# FW2-17-LEDLevelDisplay.net
KiCad netlist of a schematic drawn in EAGLE
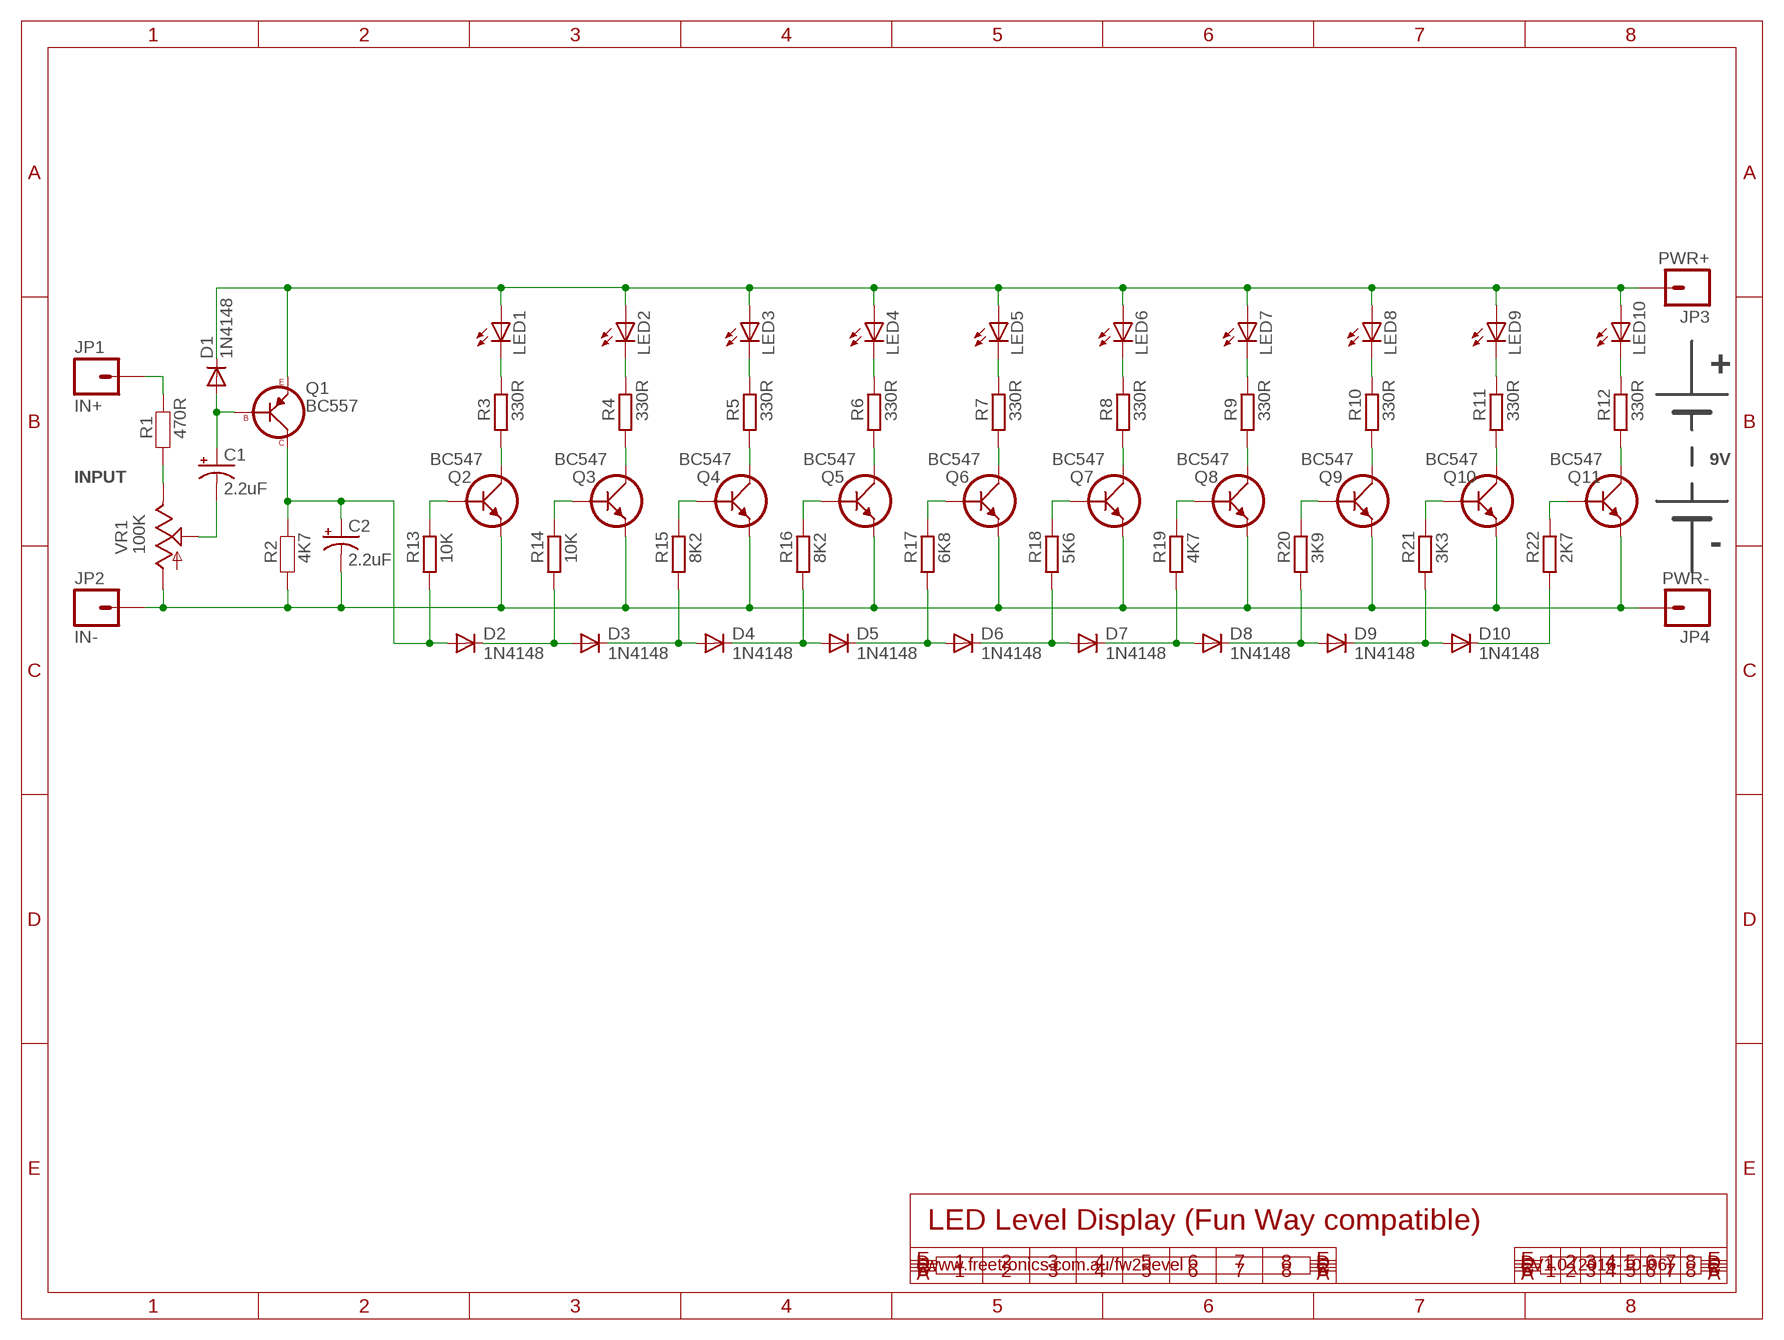
[diagram p0: schematic, sheet 1]

(export (version "E")
  (design (tool "Eeschema 10.0.6"))
  (components
    (comp (ref "C1")
      (value "2.2uF")
      (footprint "eagle-import:CPOL-RADIAL-100UF-25V")
      (libsource (lib "eagle-import") (part "CAP_POLPTH1"))
    )
    (comp (ref "C2")
      (value "2.2uF")
      (footprint "eagle-import:CPOL-RADIAL-100UF-25V")
      (libsource (lib "eagle-import") (part "CAP_POLPTH1"))
    )
    (comp (ref "D1")
      (value "1N4148")
      (footprint "eagle-import:DIODE-1N914")
      (libsource (lib "eagle-import") (part "DIODE1N914"))
    )
    (comp (ref "D2")
      (value "1N4148")
      (footprint "eagle-import:DIODE-1N914")
      (libsource (lib "eagle-import") (part "DIODE1N914"))
    )
    (comp (ref "D3")
      (value "1N4148")
      (footprint "eagle-import:DIODE-1N914")
      (libsource (lib "eagle-import") (part "DIODE1N914"))
    )
    (comp (ref "D4")
      (value "1N4148")
      (footprint "eagle-import:DIODE-1N914")
      (libsource (lib "eagle-import") (part "DIODE1N914"))
    )
    (comp (ref "D5")
      (value "1N4148")
      (footprint "eagle-import:DIODE-1N914")
      (libsource (lib "eagle-import") (part "DIODE1N914"))
    )
    (comp (ref "D6")
      (value "1N4148")
      (footprint "eagle-import:DIODE-1N914")
      (libsource (lib "eagle-import") (part "DIODE1N914"))
    )
    (comp (ref "D7")
      (value "1N4148")
      (footprint "eagle-import:DIODE-1N914")
      (libsource (lib "eagle-import") (part "DIODE1N914"))
    )
    (comp (ref "D8")
      (value "1N4148")
      (footprint "eagle-import:DIODE-1N914")
      (libsource (lib "eagle-import") (part "DIODE1N914"))
    )
    (comp (ref "D9")
      (value "1N4148")
      (footprint "eagle-import:DIODE-1N914")
      (libsource (lib "eagle-import") (part "DIODE1N914"))
    )
    (comp (ref "D10")
      (value "1N4148")
      (footprint "eagle-import:DIODE-1N914")
      (libsource (lib "eagle-import") (part "DIODE1N914"))
    )
    (comp (ref "JP1")
      (value "IN+")
      (footprint "eagle-import:1X01")
      (libsource (lib "eagle-import") (part "M01PTH"))
    )
    (comp (ref "JP2")
      (value "IN-")
      (footprint "eagle-import:1X01")
      (libsource (lib "eagle-import") (part "M01PTH"))
    )
    (comp (ref "JP3")
      (value "PWR+")
      (footprint "eagle-import:1X01")
      (libsource (lib "eagle-import") (part "M01PTH"))
    )
    (comp (ref "JP4")
      (value "PWR-")
      (footprint "eagle-import:1X01")
      (libsource (lib "eagle-import") (part "M01PTH"))
    )
    (comp (ref "LED1")
      (value "LED5MM")
      (footprint "eagle-import:LED5MM")
      (libsource (lib "eagle-import") (part "LED5MM"))
    )
    (comp (ref "LED2")
      (value "LED5MM")
      (footprint "eagle-import:LED5MM")
      (libsource (lib "eagle-import") (part "LED5MM"))
    )
    (comp (ref "LED3")
      (value "LED5MM")
      (footprint "eagle-import:LED5MM")
      (libsource (lib "eagle-import") (part "LED5MM"))
    )
    (comp (ref "LED4")
      (value "LED5MM")
      (footprint "eagle-import:LED5MM")
      (libsource (lib "eagle-import") (part "LED5MM"))
    )
    (comp (ref "LED5")
      (value "LED5MM")
      (footprint "eagle-import:LED5MM")
      (libsource (lib "eagle-import") (part "LED5MM"))
    )
    (comp (ref "LED6")
      (value "LED5MM")
      (footprint "eagle-import:LED5MM")
      (libsource (lib "eagle-import") (part "LED5MM"))
    )
    (comp (ref "LED7")
      (value "LED5MM")
      (footprint "eagle-import:LED5MM")
      (libsource (lib "eagle-import") (part "LED5MM"))
    )
    (comp (ref "LED8")
      (value "LED5MM")
      (footprint "eagle-import:LED5MM")
      (libsource (lib "eagle-import") (part "LED5MM"))
    )
    (comp (ref "LED9")
      (value "LED5MM")
      (footprint "eagle-import:LED5MM")
      (libsource (lib "eagle-import") (part "LED5MM"))
    )
    (comp (ref "LED10")
      (value "LED5MM")
      (footprint "eagle-import:LED5MM")
      (libsource (lib "eagle-import") (part "LED5MM"))
    )
    (comp (ref "Q1")
      (value "BC557")
      (footprint "eagle-import:TO-92")
      (libsource (lib "eagle-import") (part "BC557"))
    )
    (comp (ref "Q2")
      (value "BC547")
      (footprint "eagle-import:TO-92")
      (libsource (lib "eagle-import") (part "BC547"))
    )
    (comp (ref "Q3")
      (value "BC547")
      (footprint "eagle-import:TO-92")
      (libsource (lib "eagle-import") (part "BC547"))
    )
    (comp (ref "Q4")
      (value "BC547")
      (footprint "eagle-import:TO-92")
      (libsource (lib "eagle-import") (part "BC547"))
    )
    (comp (ref "Q5")
      (value "BC547")
      (footprint "eagle-import:TO-92")
      (libsource (lib "eagle-import") (part "BC547"))
    )
    (comp (ref "Q6")
      (value "BC547")
      (footprint "eagle-import:TO-92")
      (libsource (lib "eagle-import") (part "BC547"))
    )
    (comp (ref "Q7")
      (value "BC547")
      (footprint "eagle-import:TO-92")
      (libsource (lib "eagle-import") (part "BC547"))
    )
    (comp (ref "Q8")
      (value "BC547")
      (footprint "eagle-import:TO-92")
      (libsource (lib "eagle-import") (part "BC547"))
    )
    (comp (ref "Q9")
      (value "BC547")
      (footprint "eagle-import:TO-92")
      (libsource (lib "eagle-import") (part "BC547"))
    )
    (comp (ref "Q10")
      (value "BC547")
      (footprint "eagle-import:TO-92")
      (libsource (lib "eagle-import") (part "BC547"))
    )
    (comp (ref "Q11")
      (value "BC547")
      (footprint "eagle-import:TO-92")
      (libsource (lib "eagle-import") (part "BC547"))
    )
    (comp (ref "R1")
      (value "470R")
      (footprint "eagle-import:FREETRONICS_AXIAL-0.4")
      (libsource (lib "eagle-import") (part "FREETRONICS_RESISTORPTH2"))
    )
    (comp (ref "R2")
      (value "4K7")
      (footprint "eagle-import:FREETRONICS_AXIAL-0.4")
      (libsource (lib "eagle-import") (part "FREETRONICS_RESISTORPTH2"))
    )
    (comp (ref "R3")
      (value "330R")
      (footprint "eagle-import:0309V")
      (libsource (lib "eagle-import") (part "R-EU_0309/V"))
    )
    (comp (ref "R4")
      (value "330R")
      (footprint "eagle-import:0309V")
      (libsource (lib "eagle-import") (part "R-EU_0309/V"))
    )
    (comp (ref "R5")
      (value "330R")
      (footprint "eagle-import:0309V")
      (libsource (lib "eagle-import") (part "R-EU_0309/V"))
    )
    (comp (ref "R6")
      (value "330R")
      (footprint "eagle-import:0309V")
      (libsource (lib "eagle-import") (part "R-EU_0309/V"))
    )
    (comp (ref "R7")
      (value "330R")
      (footprint "eagle-import:0309V")
      (libsource (lib "eagle-import") (part "R-EU_0309/V"))
    )
    (comp (ref "R8")
      (value "330R")
      (footprint "eagle-import:0309V")
      (libsource (lib "eagle-import") (part "R-EU_0309/V"))
    )
    (comp (ref "R9")
      (value "330R")
      (footprint "eagle-import:0309V")
      (libsource (lib "eagle-import") (part "R-EU_0309/V"))
    )
    (comp (ref "R10")
      (value "330R")
      (footprint "eagle-import:0309V")
      (libsource (lib "eagle-import") (part "R-EU_0309/V"))
    )
    (comp (ref "R11")
      (value "330R")
      (footprint "eagle-import:0309V")
      (libsource (lib "eagle-import") (part "R-EU_0309/V"))
    )
    (comp (ref "R12")
      (value "330R")
      (footprint "eagle-import:0309V")
      (libsource (lib "eagle-import") (part "R-EU_0309/V"))
    )
    (comp (ref "R13")
      (value "10K")
      (footprint "eagle-import:0309V")
      (libsource (lib "eagle-import") (part "R-EU_0309/V"))
    )
    (comp (ref "R14")
      (value "10K")
      (footprint "eagle-import:0309V")
      (libsource (lib "eagle-import") (part "R-EU_0309/V"))
    )
    (comp (ref "R15")
      (value "8K2")
      (footprint "eagle-import:0309V")
      (libsource (lib "eagle-import") (part "R-EU_0309/V"))
    )
    (comp (ref "R16")
      (value "8K2")
      (footprint "eagle-import:0309V")
      (libsource (lib "eagle-import") (part "R-EU_0309/V"))
    )
    (comp (ref "R17")
      (value "6K8")
      (footprint "eagle-import:0309V")
      (libsource (lib "eagle-import") (part "R-EU_0309/V"))
    )
    (comp (ref "R18")
      (value "5K6")
      (footprint "eagle-import:0309V")
      (libsource (lib "eagle-import") (part "R-EU_0309/V"))
    )
    (comp (ref "R19")
      (value "4K7")
      (footprint "eagle-import:0309V")
      (libsource (lib "eagle-import") (part "R-EU_0309/V"))
    )
    (comp (ref "R20")
      (value "3K9")
      (footprint "eagle-import:0309V")
      (libsource (lib "eagle-import") (part "R-EU_0309/V"))
    )
    (comp (ref "R21")
      (value "3K3")
      (footprint "eagle-import:0309V")
      (libsource (lib "eagle-import") (part "R-EU_0309/V"))
    )
    (comp (ref "R22")
      (value "2K7")
      (footprint "eagle-import:0309V")
      (libsource (lib "eagle-import") (part "R-EU_0309/V"))
    )
    (comp (ref "VR1")
      (value "100K")
      (footprint "eagle-import:6MM")
      (libsource (lib "eagle-import") (part "TRIM"))
    )
  )
  (nets
    (net (code "1") (name "Net-(C1-+)") (class "Default")
      (node (ref "C1") (pin "1") (pinfunction "+_1") (pintype "passive"))
      (node (ref "D1") (pin "A") (pinfunction "A_A") (pintype "passive"))
      (node (ref "Q1") (pin "2") (pinfunction "B_2") (pintype "passive"))
    )
    (net (code "2") (name "Net-(C1--)") (class "Default")
      (node (ref "C1") (pin "2") (pinfunction "-_2") (pintype "passive"))
      (node (ref "VR1") (pin "S") (pinfunction "S_S") (pintype "passive"))
    )
    (net (code "3") (name "Net-(C2-+)") (class "Default")
      (node (ref "C2") (pin "1") (pinfunction "+_1") (pintype "passive"))
      (node (ref "D2") (pin "A") (pinfunction "A_A") (pintype "passive"))
      (node (ref "Q1") (pin "1") (pinfunction "C_1") (pintype "passive"))
      (node (ref "R13") (pin "1") (pinfunction "1_1") (pintype "passive"))
      (node (ref "R2") (pin "P$2") (pinfunction "2_P$2") (pintype "passive"))
    )
    (net (code "4") (name "Net-(C2--)") (class "Default")
      (node (ref "C2") (pin "2") (pinfunction "-_2") (pintype "passive"))
      (node (ref "JP2") (pin "1") (pinfunction "1_1") (pintype "passive"))
      (node (ref "JP4") (pin "1") (pinfunction "1_1") (pintype "passive"))
      (node (ref "Q10") (pin "3") (pinfunction "E_3") (pintype "passive"))
      (node (ref "Q11") (pin "3") (pinfunction "E_3") (pintype "passive"))
      (node (ref "Q2") (pin "3") (pinfunction "E_3") (pintype "passive"))
      (node (ref "Q3") (pin "3") (pinfunction "E_3") (pintype "passive"))
      (node (ref "Q4") (pin "3") (pinfunction "E_3") (pintype "passive"))
      (node (ref "Q5") (pin "3") (pinfunction "E_3") (pintype "passive"))
      (node (ref "Q6") (pin "3") (pinfunction "E_3") (pintype "passive"))
      (node (ref "Q7") (pin "3") (pinfunction "E_3") (pintype "passive"))
      (node (ref "Q8") (pin "3") (pinfunction "E_3") (pintype "passive"))
      (node (ref "Q9") (pin "3") (pinfunction "E_3") (pintype "passive"))
      (node (ref "R2") (pin "P$1") (pinfunction "1_P$1") (pintype "passive"))
      (node (ref "VR1") (pin "A") (pinfunction "A_A") (pintype "passive"))
    )
    (net (code "5") (name "Net-(D2-PadC)") (class "Default")
      (node (ref "D2") (pin "C") (pinfunction "C_C") (pintype "passive"))
      (node (ref "D3") (pin "A") (pinfunction "A_A") (pintype "passive"))
      (node (ref "R14") (pin "1") (pinfunction "1_1") (pintype "passive"))
    )
    (net (code "6") (name "Net-(D3-PadC)") (class "Default")
      (node (ref "D3") (pin "C") (pinfunction "C_C") (pintype "passive"))
      (node (ref "D4") (pin "A") (pinfunction "A_A") (pintype "passive"))
      (node (ref "R15") (pin "1") (pinfunction "1_1") (pintype "passive"))
    )
    (net (code "7") (name "Net-(D4-PadC)") (class "Default")
      (node (ref "D4") (pin "C") (pinfunction "C_C") (pintype "passive"))
      (node (ref "D5") (pin "A") (pinfunction "A_A") (pintype "passive"))
      (node (ref "R16") (pin "1") (pinfunction "1_1") (pintype "passive"))
    )
    (net (code "8") (name "Net-(D5-PadC)") (class "Default")
      (node (ref "D5") (pin "C") (pinfunction "C_C") (pintype "passive"))
      (node (ref "D6") (pin "A") (pinfunction "A_A") (pintype "passive"))
      (node (ref "R17") (pin "1") (pinfunction "1_1") (pintype "passive"))
    )
    (net (code "9") (name "Net-(D6-PadC)") (class "Default")
      (node (ref "D6") (pin "C") (pinfunction "C_C") (pintype "passive"))
      (node (ref "D7") (pin "A") (pinfunction "A_A") (pintype "passive"))
      (node (ref "R18") (pin "1") (pinfunction "1_1") (pintype "passive"))
    )
    (net (code "10") (name "Net-(D7-PadC)") (class "Default")
      (node (ref "D7") (pin "C") (pinfunction "C_C") (pintype "passive"))
      (node (ref "D8") (pin "A") (pinfunction "A_A") (pintype "passive"))
      (node (ref "R19") (pin "1") (pinfunction "1_1") (pintype "passive"))
    )
    (net (code "11") (name "Net-(D8-PadC)") (class "Default")
      (node (ref "D8") (pin "C") (pinfunction "C_C") (pintype "passive"))
      (node (ref "D9") (pin "A") (pinfunction "A_A") (pintype "passive"))
      (node (ref "R20") (pin "1") (pinfunction "1_1") (pintype "passive"))
    )
    (net (code "12") (name "Net-(D10-PadA)") (class "Default")
      (node (ref "D10") (pin "A") (pinfunction "A_A") (pintype "passive"))
      (node (ref "D9") (pin "C") (pinfunction "C_C") (pintype "passive"))
      (node (ref "R21") (pin "1") (pinfunction "1_1") (pintype "passive"))
    )
    (net (code "13") (name "Net-(D10-PadC)") (class "Default")
      (node (ref "D10") (pin "C") (pinfunction "C_C") (pintype "passive"))
      (node (ref "R22") (pin "1") (pinfunction "1_1") (pintype "passive"))
    )
    (net (code "14") (name "Net-(LED1-C)") (class "Default")
      (node (ref "LED1") (pin "K") (pinfunction "C_K") (pintype "passive"))
      (node (ref "R3") (pin "1") (pinfunction "1_1") (pintype "passive"))
    )
    (net (code "15") (name "Net-(LED2-C)") (class "Default")
      (node (ref "LED2") (pin "K") (pinfunction "C_K") (pintype "passive"))
      (node (ref "R4") (pin "1") (pinfunction "1_1") (pintype "passive"))
    )
    (net (code "16") (name "Net-(LED3-C)") (class "Default")
      (node (ref "LED3") (pin "K") (pinfunction "C_K") (pintype "passive"))
      (node (ref "R5") (pin "1") (pinfunction "1_1") (pintype "passive"))
    )
    (net (code "17") (name "Net-(LED4-C)") (class "Default")
      (node (ref "LED4") (pin "K") (pinfunction "C_K") (pintype "passive"))
      (node (ref "R6") (pin "1") (pinfunction "1_1") (pintype "passive"))
    )
    (net (code "18") (name "Net-(LED5-C)") (class "Default")
      (node (ref "LED5") (pin "K") (pinfunction "C_K") (pintype "passive"))
      (node (ref "R7") (pin "1") (pinfunction "1_1") (pintype "passive"))
    )
    (net (code "19") (name "Net-(LED6-C)") (class "Default")
      (node (ref "LED6") (pin "K") (pinfunction "C_K") (pintype "passive"))
      (node (ref "R8") (pin "1") (pinfunction "1_1") (pintype "passive"))
    )
    (net (code "20") (name "Net-(LED7-C)") (class "Default")
      (node (ref "LED7") (pin "K") (pinfunction "C_K") (pintype "passive"))
      (node (ref "R9") (pin "1") (pinfunction "1_1") (pintype "passive"))
    )
    (net (code "21") (name "Net-(LED8-C)") (class "Default")
      (node (ref "LED8") (pin "K") (pinfunction "C_K") (pintype "passive"))
      (node (ref "R10") (pin "1") (pinfunction "1_1") (pintype "passive"))
    )
    (net (code "22") (name "Net-(LED9-C)") (class "Default")
      (node (ref "LED9") (pin "K") (pinfunction "C_K") (pintype "passive"))
      (node (ref "R11") (pin "1") (pinfunction "1_1") (pintype "passive"))
    )
    (net (code "23") (name "Net-(LED10-C)") (class "Default")
      (node (ref "LED10") (pin "K") (pinfunction "C_K") (pintype "passive"))
      (node (ref "R12") (pin "1") (pinfunction "1_1") (pintype "passive"))
    )
    (net (code "24") (name "Net-(Q1-E)") (class "Default")
      (node (ref "D1") (pin "C") (pinfunction "C_C") (pintype "passive"))
      (node (ref "JP3") (pin "1") (pinfunction "1_1") (pintype "passive"))
      (node (ref "LED1") (pin "A") (pinfunction "A_A") (pintype "passive"))
      (node (ref "LED10") (pin "A") (pinfunction "A_A") (pintype "passive"))
      (node (ref "LED2") (pin "A") (pinfunction "A_A") (pintype "passive"))
      (node (ref "LED3") (pin "A") (pinfunction "A_A") (pintype "passive"))
      (node (ref "LED4") (pin "A") (pinfunction "A_A") (pintype "passive"))
      (node (ref "LED5") (pin "A") (pinfunction "A_A") (pintype "passive"))
      (node (ref "LED6") (pin "A") (pinfunction "A_A") (pintype "passive"))
      (node (ref "LED7") (pin "A") (pinfunction "A_A") (pintype "passive"))
      (node (ref "LED8") (pin "A") (pinfunction "A_A") (pintype "passive"))
      (node (ref "LED9") (pin "A") (pinfunction "A_A") (pintype "passive"))
      (node (ref "Q1") (pin "3") (pinfunction "E_3") (pintype "passive"))
    )
    (net (code "25") (name "Net-(Q2-B)") (class "Default")
      (node (ref "Q2") (pin "2") (pinfunction "B_2") (pintype "passive"))
      (node (ref "R13") (pin "2") (pinfunction "2_2") (pintype "passive"))
    )
    (net (code "26") (name "Net-(Q2-C)") (class "Default")
      (node (ref "Q2") (pin "1") (pinfunction "C_1") (pintype "passive"))
      (node (ref "R3") (pin "2") (pinfunction "2_2") (pintype "passive"))
    )
    (net (code "27") (name "Net-(Q3-B)") (class "Default")
      (node (ref "Q3") (pin "2") (pinfunction "B_2") (pintype "passive"))
      (node (ref "R14") (pin "2") (pinfunction "2_2") (pintype "passive"))
    )
    (net (code "28") (name "Net-(Q3-C)") (class "Default")
      (node (ref "Q3") (pin "1") (pinfunction "C_1") (pintype "passive"))
      (node (ref "R4") (pin "2") (pinfunction "2_2") (pintype "passive"))
    )
    (net (code "29") (name "Net-(Q4-B)") (class "Default")
      (node (ref "Q4") (pin "2") (pinfunction "B_2") (pintype "passive"))
      (node (ref "R15") (pin "2") (pinfunction "2_2") (pintype "passive"))
    )
    (net (code "30") (name "Net-(Q4-C)") (class "Default")
      (node (ref "Q4") (pin "1") (pinfunction "C_1") (pintype "passive"))
      (node (ref "R5") (pin "2") (pinfunction "2_2") (pintype "passive"))
    )
    (net (code "31") (name "Net-(Q5-B)") (class "Default")
      (node (ref "Q5") (pin "2") (pinfunction "B_2") (pintype "passive"))
      (node (ref "R16") (pin "2") (pinfunction "2_2") (pintype "passive"))
    )
    (net (code "32") (name "Net-(Q5-C)") (class "Default")
      (node (ref "Q5") (pin "1") (pinfunction "C_1") (pintype "passive"))
      (node (ref "R6") (pin "2") (pinfunction "2_2") (pintype "passive"))
    )
    (net (code "33") (name "Net-(Q6-B)") (class "Default")
      (node (ref "Q6") (pin "2") (pinfunction "B_2") (pintype "passive"))
      (node (ref "R17") (pin "2") (pinfunction "2_2") (pintype "passive"))
    )
    (net (code "34") (name "Net-(Q6-C)") (class "Default")
      (node (ref "Q6") (pin "1") (pinfunction "C_1") (pintype "passive"))
      (node (ref "R7") (pin "2") (pinfunction "2_2") (pintype "passive"))
    )
    (net (code "35") (name "Net-(Q7-B)") (class "Default")
      (node (ref "Q7") (pin "2") (pinfunction "B_2") (pintype "passive"))
      (node (ref "R18") (pin "2") (pinfunction "2_2") (pintype "passive"))
    )
    (net (code "36") (name "Net-(Q7-C)") (class "Default")
      (node (ref "Q7") (pin "1") (pinfunction "C_1") (pintype "passive"))
      (node (ref "R8") (pin "2") (pinfunction "2_2") (pintype "passive"))
    )
    (net (code "37") (name "Net-(Q8-B)") (class "Default")
      (node (ref "Q8") (pin "2") (pinfunction "B_2") (pintype "passive"))
      (node (ref "R19") (pin "2") (pinfunction "2_2") (pintype "passive"))
    )
    (net (code "38") (name "Net-(Q8-C)") (class "Default")
      (node (ref "Q8") (pin "1") (pinfunction "C_1") (pintype "passive"))
      (node (ref "R9") (pin "2") (pinfunction "2_2") (pintype "passive"))
    )
    (net (code "39") (name "Net-(Q9-B)") (class "Default")
      (node (ref "Q9") (pin "2") (pinfunction "B_2") (pintype "passive"))
      (node (ref "R20") (pin "2") (pinfunction "2_2") (pintype "passive"))
    )
    (net (code "40") (name "Net-(Q9-C)") (class "Default")
      (node (ref "Q9") (pin "1") (pinfunction "C_1") (pintype "passive"))
      (node (ref "R10") (pin "2") (pinfunction "2_2") (pintype "passive"))
    )
    (net (code "41") (name "Net-(Q10-B)") (class "Default")
      (node (ref "Q10") (pin "2") (pinfunction "B_2") (pintype "passive"))
      (node (ref "R21") (pin "2") (pinfunction "2_2") (pintype "passive"))
    )
    (net (code "42") (name "Net-(Q10-C)") (class "Default")
      (node (ref "Q10") (pin "1") (pinfunction "C_1") (pintype "passive"))
      (node (ref "R11") (pin "2") (pinfunction "2_2") (pintype "passive"))
    )
    (net (code "43") (name "Net-(Q11-B)") (class "Default")
      (node (ref "Q11") (pin "2") (pinfunction "B_2") (pintype "passive"))
      (node (ref "R22") (pin "2") (pinfunction "2_2") (pintype "passive"))
    )
    (net (code "44") (name "Net-(Q11-C)") (class "Default")
      (node (ref "Q11") (pin "1") (pinfunction "C_1") (pintype "passive"))
      (node (ref "R12") (pin "2") (pinfunction "2_2") (pintype "passive"))
    )
    (net (code "45") (name "Net-(R1-1)") (class "Default")
      (node (ref "R1") (pin "P$1") (pinfunction "1_P$1") (pintype "passive"))
      (node (ref "VR1") (pin "E") (pinfunction "E_E") (pintype "passive"))
    )
    (net (code "46") (name "Net-(R1-2)") (class "Default")
      (node (ref "JP1") (pin "1") (pinfunction "1_1") (pintype "passive"))
      (node (ref "R1") (pin "P$2") (pinfunction "2_P$2") (pintype "passive"))
    )
  )
)
